# Lm7704.net
KiCad netlist of a schematic drawn in EAGLE
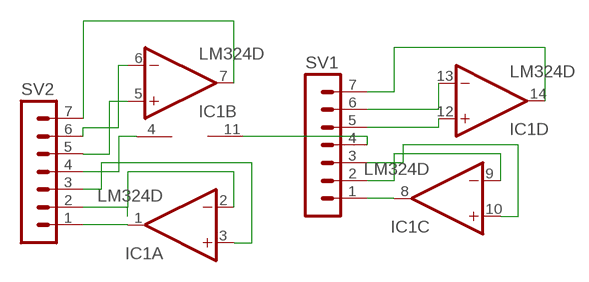
[diagram p0: schematic, sheet 1]

(export (version "E")
  (design (tool "Eeschema 10.0.6"))
  (components
    (comp (ref "IC1")
      (value "LM324D")
      (footprint "eagle-import:SO14")
      (libsource (lib "eagle-import") (part "LM324D"))
    )
    (comp (ref "SV1")
      (value "MA07-1")
      (footprint "eagle-import:MA07-1")
      (libsource (lib "eagle-import") (part "MA07-1"))
    )
    (comp (ref "SV2")
      (value "MA07-1")
      (footprint "eagle-import:MA07-1")
      (libsource (lib "eagle-import") (part "MA07-1"))
    )
  )
  (nets
    (net (code "1") (name "Net-(IC1A-+IN)") (class "Default")
      (node (ref "IC1") (pin "3") (pinfunction "+IN_3") (pintype "input"))
      (node (ref "SV2") (pin "3") (pinfunction "3_3") (pintype "passive"))
    )
    (net (code "2") (name "Net-(IC1A--IN)") (class "Default")
      (node (ref "IC1") (pin "2") (pinfunction "-IN_2") (pintype "input"))
      (node (ref "SV2") (pin "2") (pinfunction "2_2") (pintype "passive"))
    )
    (net (code "3") (name "Net-(IC1A-OUT)") (class "Default")
      (node (ref "IC1") (pin "1") (pinfunction "OUT_1") (pintype "output"))
      (node (ref "SV2") (pin "1") (pinfunction "1_1") (pintype "passive"))
    )
    (net (code "4") (name "Net-(IC1B-+IN)") (class "Default")
      (node (ref "IC1") (pin "5") (pinfunction "+IN_5") (pintype "input"))
      (node (ref "SV2") (pin "5") (pinfunction "5_5") (pintype "passive"))
    )
    (net (code "5") (name "Net-(IC1B--IN)") (class "Default")
      (node (ref "IC1") (pin "6") (pinfunction "-IN_6") (pintype "input"))
      (node (ref "SV2") (pin "6") (pinfunction "6_6") (pintype "passive"))
    )
    (net (code "6") (name "Net-(IC1B-OUT)") (class "Default")
      (node (ref "IC1") (pin "7") (pinfunction "OUT_7") (pintype "output"))
      (node (ref "SV2") (pin "7") (pinfunction "7_7") (pintype "passive"))
    )
    (net (code "7") (name "Net-(IC1C-+IN)") (class "Default")
      (node (ref "IC1") (pin "10") (pinfunction "+IN_10") (pintype "input"))
      (node (ref "SV1") (pin "3") (pinfunction "3_3") (pintype "passive"))
    )
    (net (code "8") (name "Net-(IC1C--IN)") (class "Default")
      (node (ref "IC1") (pin "9") (pinfunction "-IN_9") (pintype "input"))
      (node (ref "SV1") (pin "2") (pinfunction "2_2") (pintype "passive"))
    )
    (net (code "9") (name "Net-(IC1C-OUT)") (class "Default")
      (node (ref "IC1") (pin "8") (pinfunction "OUT_8") (pintype "output"))
      (node (ref "SV1") (pin "1") (pinfunction "1_1") (pintype "passive"))
    )
    (net (code "10") (name "Net-(IC1D-+IN)") (class "Default")
      (node (ref "IC1") (pin "12") (pinfunction "+IN_12") (pintype "input"))
      (node (ref "SV1") (pin "5") (pinfunction "5_5") (pintype "passive"))
    )
    (net (code "11") (name "Net-(IC1D--IN)") (class "Default")
      (node (ref "IC1") (pin "13") (pinfunction "-IN_13") (pintype "input"))
      (node (ref "SV1") (pin "6") (pinfunction "6_6") (pintype "passive"))
    )
    (net (code "12") (name "Net-(IC1D-OUT)") (class "Default")
      (node (ref "IC1") (pin "14") (pinfunction "OUT_14") (pintype "output"))
      (node (ref "SV1") (pin "7") (pinfunction "7_7") (pintype "passive"))
    )
    (net (code "13") (name "Net-(IC1E-V+)") (class "Default")
      (node (ref "IC1") (pin "4") (pinfunction "V+_4") (pintype "power_in"))
      (node (ref "SV2") (pin "4") (pinfunction "4_4") (pintype "passive"))
    )
    (net (code "14") (name "Net-(IC1E-V-)") (class "Default")
      (node (ref "IC1") (pin "11") (pinfunction "V-_11") (pintype "power_in"))
      (node (ref "SV1") (pin "4") (pinfunction "4_4") (pintype "passive"))
    )
  )
)
